# Arduino_Breakout_Shield.net
KiCad netlist of a schematic drawn in EAGLE
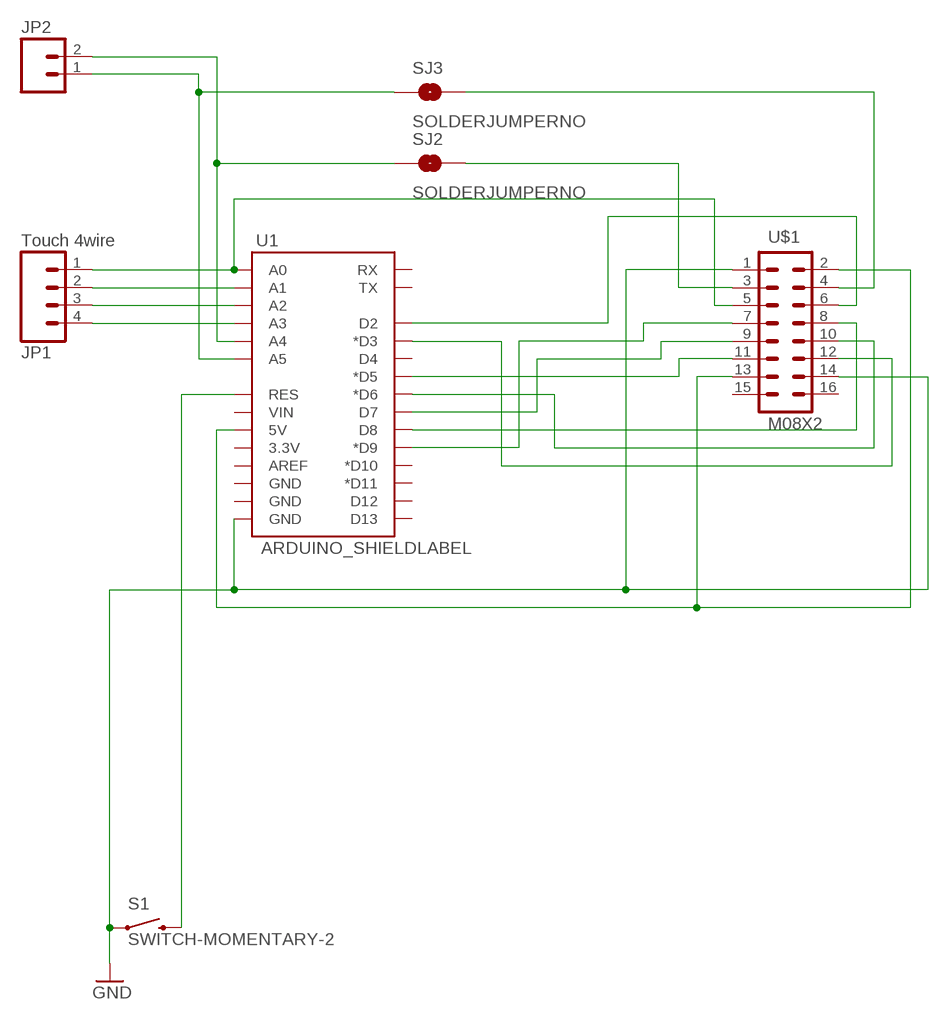
[diagram p0: schematic, sheet 1]

(export (version "E")
  (design (tool "Eeschema 10.0.6"))
  (components
    (comp (ref "JP1")
      (value "Touch 4wire")
      (footprint "eagle-import:1X04")
      (libsource (lib "eagle-import") (part "M04PTH"))
    )
    (comp (ref "JP2")
      (value "M02PTH")
      (footprint "eagle-import:1X02")
      (libsource (lib "eagle-import") (part "M02PTH"))
    )
    (comp (ref "S1")
      (value "SWITCH-MOMENTARY-2")
      (footprint "eagle-import:TACTILE_SWITCH_TALL")
      (libsource (lib "eagle-import") (part "SWITCH-MOMENTARY-2"))
    )
    (comp (ref "SJ2")
      (value "SOLDERJUMPERNO")
      (footprint "eagle-import:SJ_2S-NO")
      (libsource (lib "eagle-import") (part "SOLDERJUMPERNO"))
    )
    (comp (ref "SJ3")
      (value "SOLDERJUMPERNO")
      (footprint "eagle-import:SJ_2S-NO")
      (libsource (lib "eagle-import") (part "SOLDERJUMPERNO"))
    )
    (comp (ref "U$1")
      (value "M08X2")
      (footprint "eagle-import:2X8")
      (libsource (lib "eagle-import") (part "M08X2"))
    )
    (comp (ref "U1")
      (value "ARDUINO_SHIELDLABEL")
      (footprint "eagle-import:DUEMILANOVE_SHIELD")
      (libsource (lib "eagle-import") (part "ARDUINO_SHIELDLABEL"))
    )
  )
  (nets
    (net (code "1") (name "GND") (class "Default")
      (node (ref "S1") (pin "A2") (pinfunction "1_A2") (pintype "passive"))
      (node (ref "U$1") (pin "1") (pinfunction "1_1") (pintype "passive"))
      (node (ref "U$1") (pin "14") (pinfunction "14_14") (pintype "passive"))
      (node (ref "U1") (pin "GND@0") (pinfunction "GND_GND@0") (pintype "bidirectional"))
    )
    (net (code "2") (name "Net-(JP1-Pad1)") (class "Default")
      (node (ref "JP1") (pin "1") (pinfunction "1_1") (pintype "passive"))
      (node (ref "U$1") (pin "5") (pinfunction "5_5") (pintype "passive"))
      (node (ref "U1") (pin "A0") (pinfunction "A0_A0") (pintype "bidirectional"))
    )
    (net (code "3") (name "Net-(JP1-Pad2)") (class "Default")
      (node (ref "JP1") (pin "2") (pinfunction "2_2") (pintype "passive"))
      (node (ref "U1") (pin "A1") (pinfunction "A1_A1") (pintype "bidirectional"))
    )
    (net (code "4") (name "Net-(JP1-Pad3)") (class "Default")
      (node (ref "JP1") (pin "3") (pinfunction "3_3") (pintype "passive"))
      (node (ref "U1") (pin "A2") (pinfunction "A2_A2") (pintype "bidirectional"))
    )
    (net (code "5") (name "Net-(JP1-Pad4)") (class "Default")
      (node (ref "JP1") (pin "4") (pinfunction "4_4") (pintype "passive"))
      (node (ref "U1") (pin "A3") (pinfunction "A3_A3") (pintype "bidirectional"))
    )
    (net (code "6") (name "Net-(JP2-Pad1)") (class "Default")
      (node (ref "JP2") (pin "1") (pinfunction "1_1") (pintype "passive"))
      (node (ref "SJ3") (pin "1") (pinfunction "1_1") (pintype "passive"))
      (node (ref "U1") (pin "A5") (pinfunction "A5_A5") (pintype "bidirectional"))
    )
    (net (code "7") (name "Net-(JP2-Pad2)") (class "Default")
      (node (ref "JP2") (pin "2") (pinfunction "2_2") (pintype "passive"))
      (node (ref "SJ2") (pin "1") (pinfunction "1_1") (pintype "passive"))
      (node (ref "U1") (pin "A4") (pinfunction "A4_A4") (pintype "bidirectional"))
    )
    (net (code "8") (name "Net-(S1-2)") (class "Default")
      (node (ref "S1") (pin "B2") (pinfunction "2_B2") (pintype "passive"))
      (node (ref "U1") (pin "RES") (pinfunction "RES_RES") (pintype "bidirectional"))
    )
    (net (code "9") (name "Net-(SJ2-Pad2)") (class "Default")
      (node (ref "SJ2") (pin "2") (pinfunction "2_2") (pintype "passive"))
      (node (ref "U$1") (pin "3") (pinfunction "3_3") (pintype "passive"))
    )
    (net (code "10") (name "Net-(SJ3-Pad2)") (class "Default")
      (node (ref "SJ3") (pin "2") (pinfunction "2_2") (pintype "passive"))
      (node (ref "U$1") (pin "4") (pinfunction "4_4") (pintype "passive"))
    )
    (net (code "11") (name "Net-(U$1-Pad6)") (class "Default")
      (node (ref "U$1") (pin "6") (pinfunction "6_6") (pintype "passive"))
      (node (ref "U1") (pin "D2") (pinfunction "D2_D2") (pintype "bidirectional"))
    )
    (net (code "12") (name "Net-(U$1-Pad8)") (class "Default")
      (node (ref "U$1") (pin "8") (pinfunction "8_8") (pintype "passive"))
      (node (ref "U1") (pin "D8") (pinfunction "D8_D8") (pintype "bidirectional"))
    )
    (net (code "13") (name "Net-(U$1-Pad9)") (class "Default")
      (node (ref "U$1") (pin "9") (pinfunction "9_9") (pintype "passive"))
      (node (ref "U1") (pin "D7") (pinfunction "D7_D7") (pintype "bidirectional"))
    )
    (net (code "14") (name "Net-(U$1-Pad13)") (class "Default")
      (node (ref "U$1") (pin "13") (pinfunction "13_13") (pintype "passive"))
      (node (ref "U$1") (pin "2") (pinfunction "2_2") (pintype "passive"))
      (node (ref "U1") (pin "5V") (pinfunction "5V_5V") (pintype "bidirectional"))
    )
    (net (code "15") (name "Net-(U1-*D3)") (class "Default")
      (node (ref "U$1") (pin "12") (pinfunction "12_12") (pintype "passive"))
      (node (ref "U1") (pin "D3") (pinfunction "*D3_D3") (pintype "bidirectional"))
    )
    (net (code "16") (name "Net-(U1-*D5)") (class "Default")
      (node (ref "U$1") (pin "11") (pinfunction "11_11") (pintype "passive"))
      (node (ref "U1") (pin "D5") (pinfunction "*D5_D5") (pintype "bidirectional"))
    )
    (net (code "17") (name "Net-(U1-*D6)") (class "Default")
      (node (ref "U$1") (pin "10") (pinfunction "10_10") (pintype "passive"))
      (node (ref "U1") (pin "D6") (pinfunction "*D6_D6") (pintype "bidirectional"))
    )
    (net (code "18") (name "Net-(U1-*D9)") (class "Default")
      (node (ref "U$1") (pin "7") (pinfunction "7_7") (pintype "passive"))
      (node (ref "U1") (pin "D9") (pinfunction "*D9_D9") (pintype "bidirectional"))
    )
    (net (code "19") (name "unconnected-(U$1-Pad15)") (class "Default")
      (node (ref "U$1") (pin "15") (pinfunction "15_15") (pintype "passive"))
    )
    (net (code "20") (name "unconnected-(U$1-Pad16)") (class "Default")
      (node (ref "U$1") (pin "16") (pinfunction "16_16") (pintype "passive"))
    )
    (net (code "21") (name "unconnected-(U1-*D10-PadD10)") (class "Default")
      (node (ref "U1") (pin "D10") (pinfunction "*D10_D10") (pintype "bidirectional"))
    )
    (net (code "22") (name "unconnected-(U1-*D11-PadD11)") (class "Default")
      (node (ref "U1") (pin "D11") (pinfunction "*D11_D11") (pintype "bidirectional"))
    )
    (net (code "23") (name "unconnected-(U1-GND-PadGND@1)") (class "Default")
      (node (ref "U1") (pin "GND@1") (pinfunction "GND_GND@1") (pintype "bidirectional"))
    )
    (net (code "24") (name "unconnected-(U1-GND-PadGND@2)") (class "Default")
      (node (ref "U1") (pin "GND@2") (pinfunction "GND_GND@2") (pintype "bidirectional"))
    )
    (net (code "25") (name "unconnected-(U1-Pad3.3V)") (class "Default")
      (node (ref "U1") (pin "3.3V") (pinfunction "3.3V_3.3V") (pintype "bidirectional"))
    )
    (net (code "26") (name "unconnected-(U1-PadAREF)") (class "Default")
      (node (ref "U1") (pin "AREF") (pinfunction "AREF_AREF") (pintype "bidirectional"))
    )
    (net (code "27") (name "unconnected-(U1-PadD4)") (class "Default")
      (node (ref "U1") (pin "D4") (pinfunction "D4_D4") (pintype "bidirectional"))
    )
    (net (code "28") (name "unconnected-(U1-PadD12)") (class "Default")
      (node (ref "U1") (pin "D12") (pinfunction "D12_D12") (pintype "bidirectional"))
    )
    (net (code "29") (name "unconnected-(U1-PadD13)") (class "Default")
      (node (ref "U1") (pin "D13") (pinfunction "D13_D13") (pintype "bidirectional"))
    )
    (net (code "30") (name "unconnected-(U1-PadRX)") (class "Default")
      (node (ref "U1") (pin "RX") (pinfunction "RX_RX") (pintype "bidirectional"))
    )
    (net (code "31") (name "unconnected-(U1-PadTX)") (class "Default")
      (node (ref "U1") (pin "TX") (pinfunction "TX_TX") (pintype "bidirectional"))
    )
    (net (code "32") (name "unconnected-(U1-PadVIN)") (class "Default")
      (node (ref "U1") (pin "VIN") (pinfunction "VIN_VIN") (pintype "bidirectional"))
    )
  )
)
